# PCB-TBAR-BOR.net
KiCad netlist of a schematic drawn in EAGLE
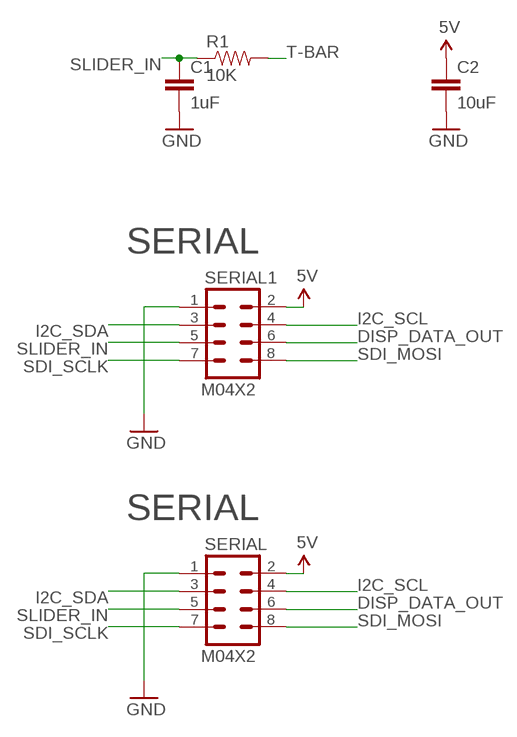
[diagram p0: schematic, sheet 1]

(export (version "E")
  (design (tool "Eeschema 10.0.6"))
  (components
    (comp (ref "C1")
      (value "1uF")
      (footprint "eagle-import:0603-CAP")
      (libsource (lib "eagle-import") (part "CAP0603-CAP"))
    )
    (comp (ref "C2")
      (value "10uF")
      (footprint "eagle-import:0805")
      (libsource (lib "eagle-import") (part "CAP0805"))
    )
    (comp (ref "R1")
      (value "10K")
      (footprint "eagle-import:0603-RES")
      (libsource (lib "eagle-import") (part "RESISTOR0603-RES"))
    )
    (comp (ref "SERIAL")
      (value "M04X2")
      (footprint "eagle-import:2X4")
      (libsource (lib "eagle-import") (part "M04X2"))
    )
    (comp (ref "SERIAL1")
      (value "M04X2")
      (footprint "eagle-import:2X4")
      (libsource (lib "eagle-import") (part "M04X2"))
    )
  )
  (nets
    (net (code "1") (name "/DISP_DATA_OUT") (class "Default")
      (node (ref "SERIAL") (pin "6") (pinfunction "6_6") (pintype "passive"))
      (node (ref "SERIAL1") (pin "6") (pinfunction "6_6") (pintype "passive"))
    )
    (net (code "2") (name "/I2C_SCL") (class "Default")
      (node (ref "SERIAL") (pin "4") (pinfunction "4_4") (pintype "passive"))
      (node (ref "SERIAL1") (pin "4") (pinfunction "4_4") (pintype "passive"))
    )
    (net (code "3") (name "/I2C_SDA") (class "Default")
      (node (ref "SERIAL") (pin "3") (pinfunction "3_3") (pintype "passive"))
      (node (ref "SERIAL1") (pin "3") (pinfunction "3_3") (pintype "passive"))
    )
    (net (code "4") (name "/SDI_MOSI") (class "Default")
      (node (ref "SERIAL") (pin "8") (pinfunction "8_8") (pintype "passive"))
      (node (ref "SERIAL1") (pin "8") (pinfunction "8_8") (pintype "passive"))
    )
    (net (code "5") (name "/SDI_SCLK") (class "Default")
      (node (ref "SERIAL") (pin "7") (pinfunction "7_7") (pintype "passive"))
      (node (ref "SERIAL1") (pin "7") (pinfunction "7_7") (pintype "passive"))
    )
    (net (code "6") (name "/SLIDER_IN") (class "Default")
      (node (ref "C1") (pin "1") (pinfunction "1_1") (pintype "passive"))
      (node (ref "R1") (pin "1") (pinfunction "1_1") (pintype "passive"))
      (node (ref "SERIAL") (pin "5") (pinfunction "5_5") (pintype "passive"))
      (node (ref "SERIAL1") (pin "5") (pinfunction "5_5") (pintype "passive"))
    )
    (net (code "7") (name "/T-BAR") (class "Default")
      (node (ref "R1") (pin "2") (pinfunction "2_2") (pintype "passive"))
    )
    (net (code "8") (name "5V") (class "Default")
      (node (ref "C2") (pin "1") (pinfunction "1_1") (pintype "passive"))
      (node (ref "SERIAL") (pin "2") (pinfunction "2_2") (pintype "passive"))
      (node (ref "SERIAL1") (pin "2") (pinfunction "2_2") (pintype "passive"))
    )
    (net (code "9") (name "GND") (class "Default")
      (node (ref "C1") (pin "2") (pinfunction "2_2") (pintype "passive"))
      (node (ref "C2") (pin "2") (pinfunction "2_2") (pintype "passive"))
      (node (ref "SERIAL") (pin "1") (pinfunction "1_1") (pintype "passive"))
      (node (ref "SERIAL1") (pin "1") (pinfunction "1_1") (pintype "passive"))
    )
  )
)
